# CANBUS_Breakout_Board.net
KiCad netlist of a schematic drawn in EAGLE
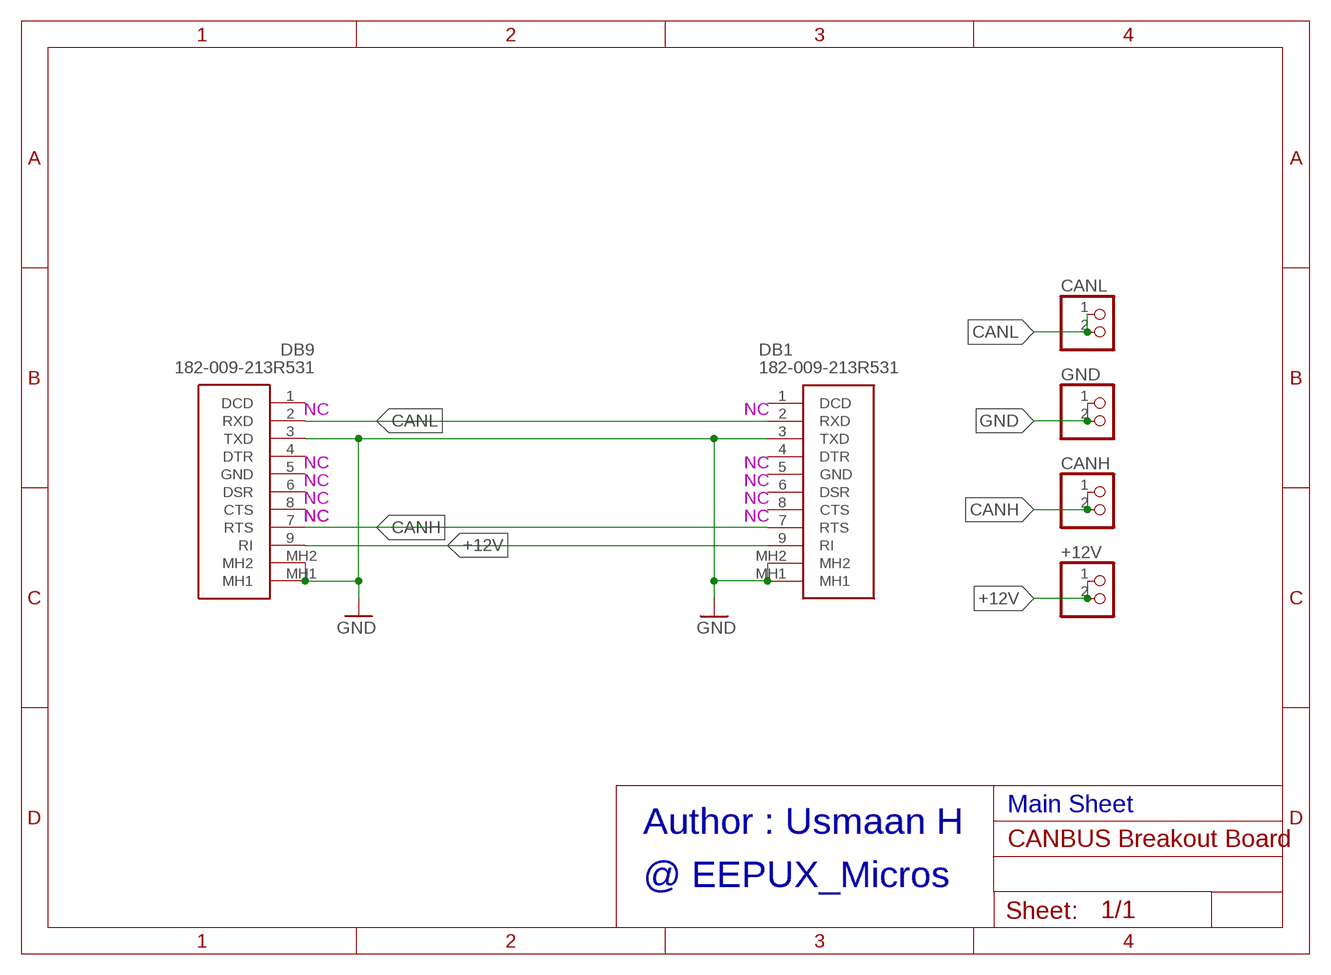
[diagram p0: schematic, sheet 1]

(export (version "E")
  (design (tool "Eeschema 10.0.6"))
  (components
    (comp (ref "+12V")
      (value "PINHD-1X2")
      (footprint "eagle-import:1X02")
      (libsource (lib "eagle-import") (part "PINHD-1X2"))
    )
    (comp (ref "CANH")
      (value "PINHD-1X2")
      (footprint "eagle-import:1X02")
      (libsource (lib "eagle-import") (part "PINHD-1X2"))
    )
    (comp (ref "CANL")
      (value "PINHD-1X2")
      (footprint "eagle-import:1X02")
      (libsource (lib "eagle-import") (part "PINHD-1X2"))
    )
    (comp (ref "DB1")
      (value "182-009-213R531")
      (footprint "eagle-import:182009213R531")
      (fields
        (field (name "MOUSER_PART_NUMBER") "636-182-009-213R531")
        (field (name "RS_PART_NUMBER") "1748825")
      )
      (libsource (lib "eagle-import") (part "182-009-213R531"))
    )
    (comp (ref "DB9")
      (value "182-009-213R531")
      (footprint "eagle-import:182009213R531")
      (fields
        (field (name "MOUSER_PART_NUMBER") "636-182-009-213R531")
        (field (name "RS_PART_NUMBER") "1748825")
      )
      (libsource (lib "eagle-import") (part "182-009-213R531"))
    )
    (comp (ref "GND")
      (value "PINHD-1X2")
      (footprint "eagle-import:1X02")
      (libsource (lib "eagle-import") (part "PINHD-1X2"))
    )
  )
  (nets
    (net (code "1") (name "+12V") (class "Default")
      (node (ref "+12V") (pin "1") (pinfunction "1_1") (pintype "passive"))
      (node (ref "+12V") (pin "2") (pinfunction "2_2") (pintype "passive"))
      (node (ref "DB1") (pin "9") (pinfunction "RI_9") (pintype "bidirectional"))
      (node (ref "DB9") (pin "9") (pinfunction "RI_9") (pintype "bidirectional"))
    )
    (net (code "2") (name "CANH") (class "Default")
      (node (ref "CANH") (pin "1") (pinfunction "1_1") (pintype "passive"))
      (node (ref "CANH") (pin "2") (pinfunction "2_2") (pintype "passive"))
      (node (ref "DB1") (pin "7") (pinfunction "RTS_7") (pintype "bidirectional"))
      (node (ref "DB9") (pin "7") (pinfunction "RTS_7") (pintype "bidirectional"))
    )
    (net (code "3") (name "CANL") (class "Default")
      (node (ref "CANL") (pin "1") (pinfunction "1_1") (pintype "passive"))
      (node (ref "CANL") (pin "2") (pinfunction "2_2") (pintype "passive"))
      (node (ref "DB1") (pin "2") (pinfunction "RXD_2") (pintype "bidirectional"))
      (node (ref "DB9") (pin "2") (pinfunction "RXD_2") (pintype "bidirectional"))
    )
    (net (code "4") (name "GND") (class "Default")
      (node (ref "DB1") (pin "3") (pinfunction "TXD_3") (pintype "bidirectional"))
      (node (ref "DB1") (pin "MH1") (pinfunction "MH1_MH1") (pintype "bidirectional"))
      (node (ref "DB1") (pin "MH2") (pinfunction "MH2_MH2") (pintype "bidirectional"))
      (node (ref "DB9") (pin "3") (pinfunction "TXD_3") (pintype "bidirectional"))
      (node (ref "DB9") (pin "MH1") (pinfunction "MH1_MH1") (pintype "bidirectional"))
      (node (ref "DB9") (pin "MH2") (pinfunction "MH2_MH2") (pintype "bidirectional"))
      (node (ref "GND") (pin "1") (pinfunction "1_1") (pintype "passive"))
      (node (ref "GND") (pin "2") (pinfunction "2_2") (pintype "passive"))
    )
    (net (code "5") (name "unconnected-(DB1-CTS-Pad8)") (class "Default")
      (node (ref "DB1") (pin "8") (pinfunction "CTS_8") (pintype "bidirectional"))
    )
    (net (code "6") (name "unconnected-(DB1-DCD-Pad1)") (class "Default")
      (node (ref "DB1") (pin "1") (pinfunction "DCD_1") (pintype "bidirectional"))
    )
    (net (code "7") (name "unconnected-(DB1-DSR-Pad6)") (class "Default")
      (node (ref "DB1") (pin "6") (pinfunction "DSR_6") (pintype "bidirectional"))
    )
    (net (code "8") (name "unconnected-(DB1-DTR-Pad4)") (class "Default")
      (node (ref "DB1") (pin "4") (pinfunction "DTR_4") (pintype "bidirectional"))
    )
    (net (code "9") (name "unconnected-(DB1-GND-Pad5)") (class "Default")
      (node (ref "DB1") (pin "5") (pinfunction "GND_5") (pintype "bidirectional"))
    )
    (net (code "10") (name "unconnected-(DB9-CTS-Pad8)") (class "Default")
      (node (ref "DB9") (pin "8") (pinfunction "CTS_8") (pintype "bidirectional"))
    )
    (net (code "11") (name "unconnected-(DB9-DCD-Pad1)") (class "Default")
      (node (ref "DB9") (pin "1") (pinfunction "DCD_1") (pintype "bidirectional"))
    )
    (net (code "12") (name "unconnected-(DB9-DSR-Pad6)") (class "Default")
      (node (ref "DB9") (pin "6") (pinfunction "DSR_6") (pintype "bidirectional"))
    )
    (net (code "13") (name "unconnected-(DB9-DTR-Pad4)") (class "Default")
      (node (ref "DB9") (pin "4") (pinfunction "DTR_4") (pintype "bidirectional"))
    )
    (net (code "14") (name "unconnected-(DB9-GND-Pad5)") (class "Default")
      (node (ref "DB9") (pin "5") (pinfunction "GND_5") (pintype "bidirectional"))
    )
  )
)
